# Mainboard.net
KiCad netlist of a schematic drawn in EAGLE
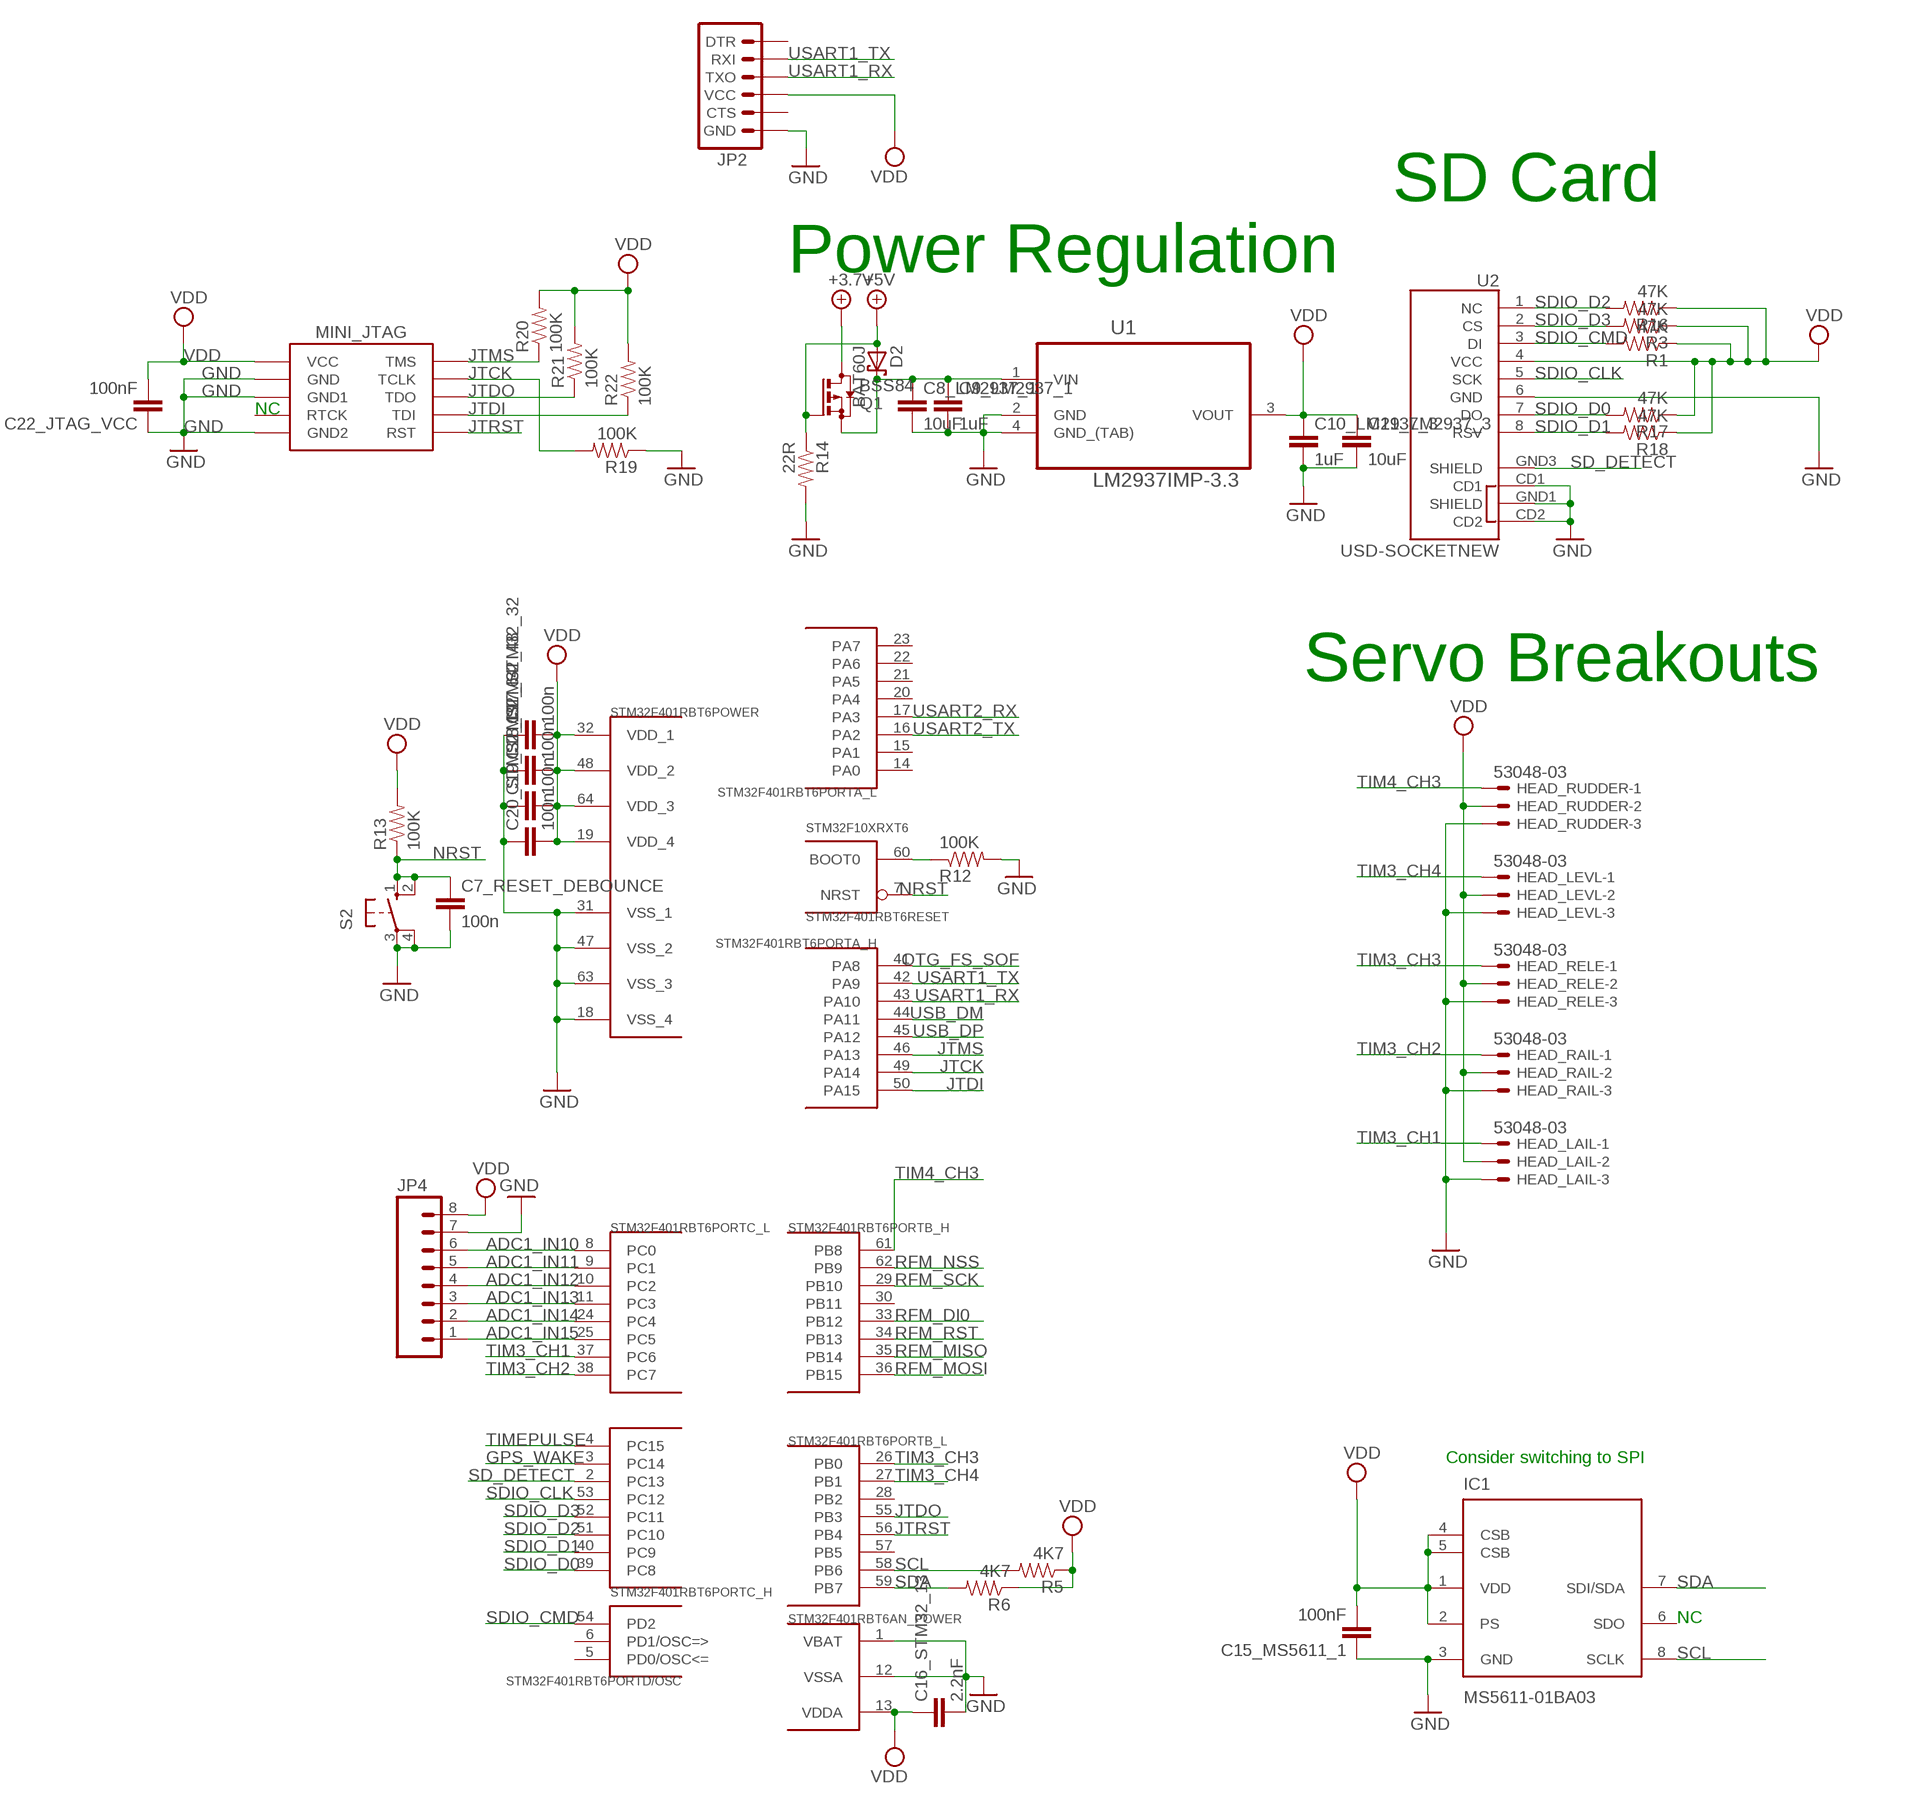
[diagram p0: schematic, sheet 1, part 1 of 2]
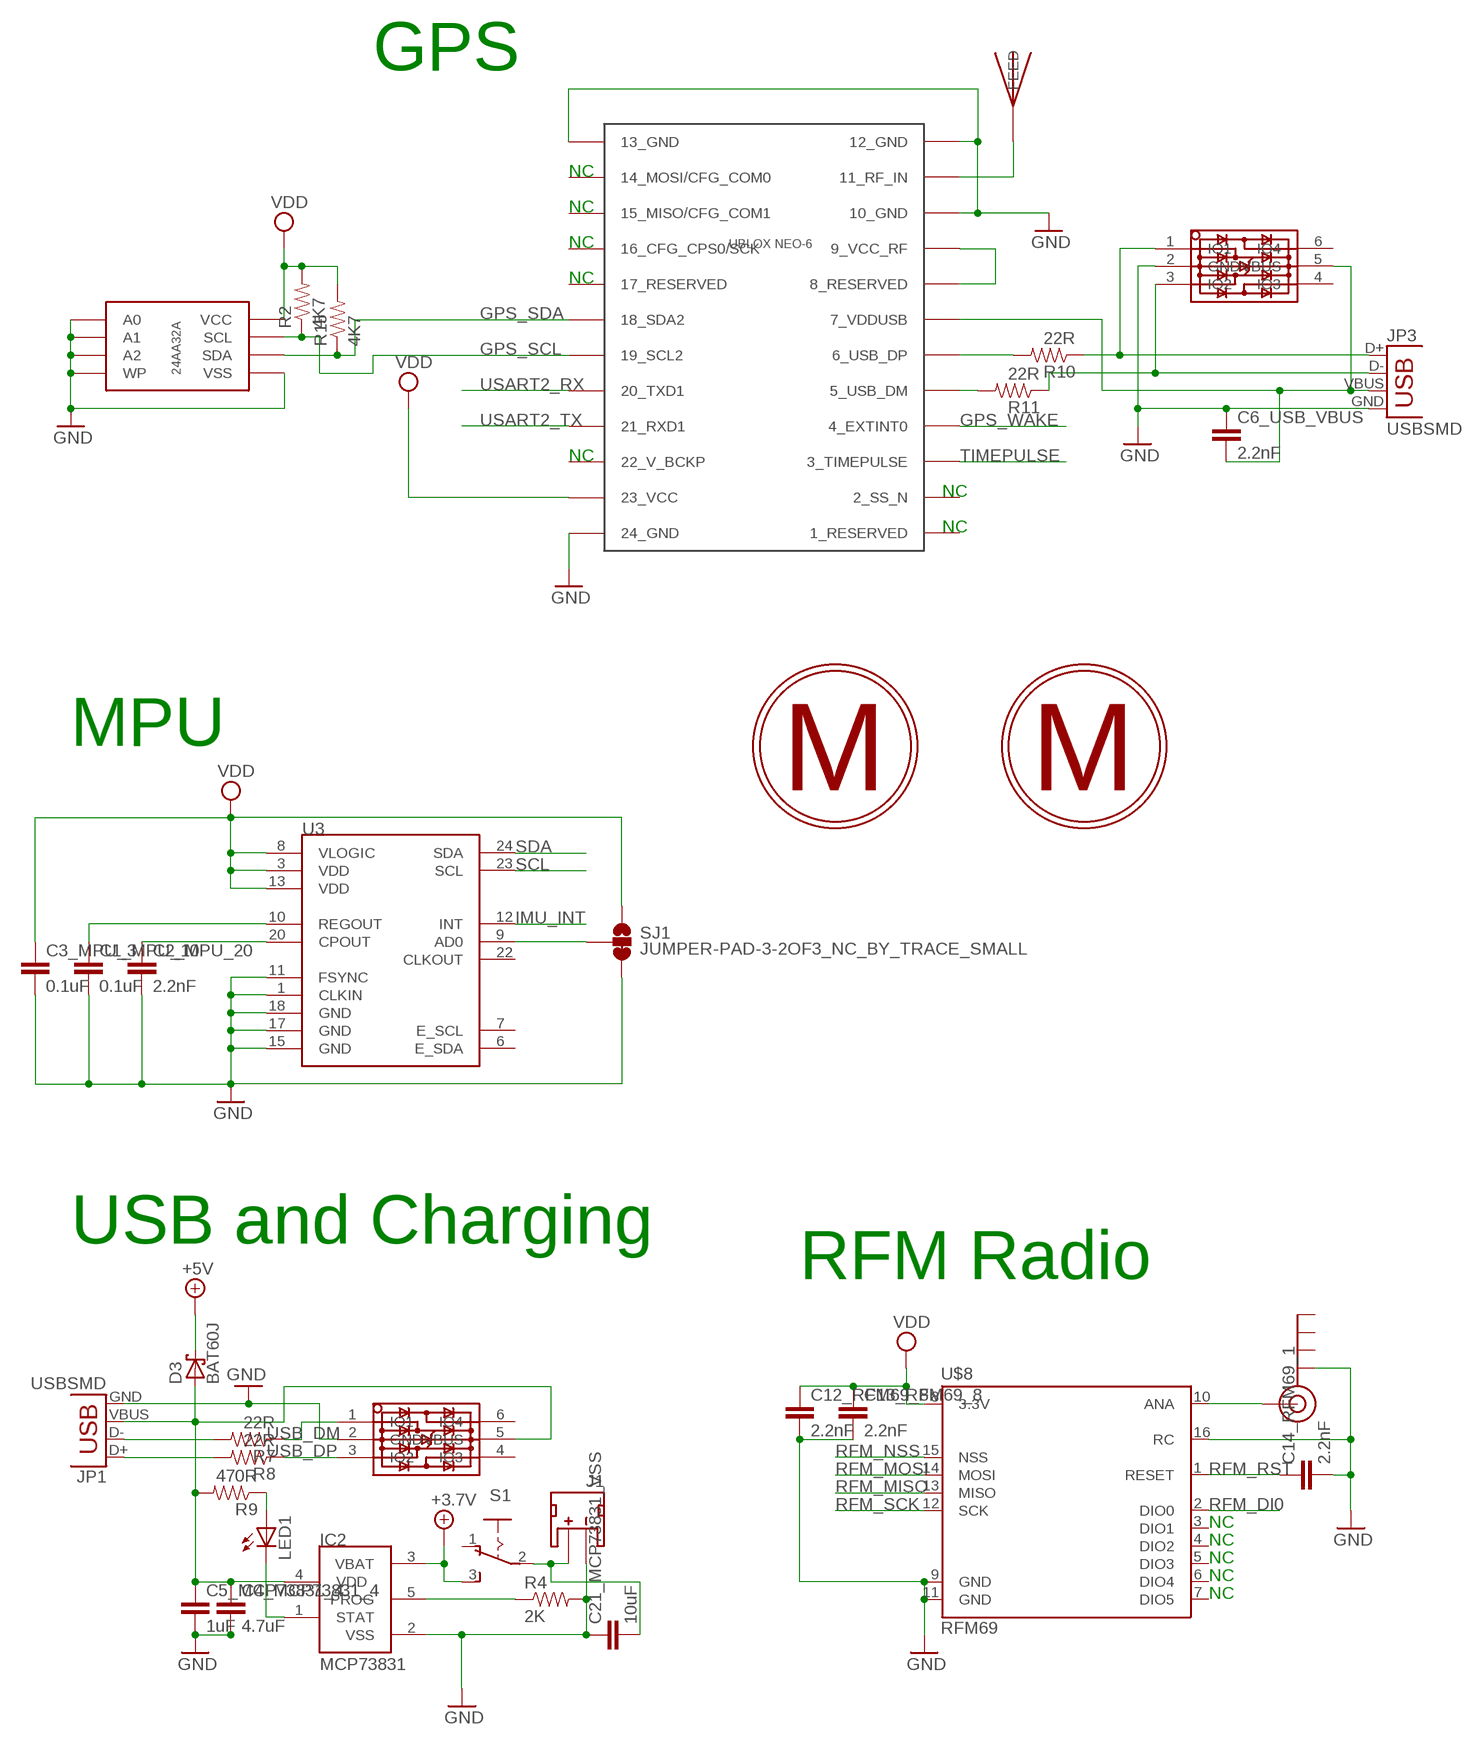
[diagram p1: schematic, sheet 1, part 2 of 2]

(export (version "E")
  (design (tool "Eeschema 10.0.6"))
  (components
    (comp (ref "C1_MPU_10")
      (value "0.1uF")
      (footprint "eagle-import:0805")
      (libsource (lib "eagle-import") (part "CAP0805"))
    )
    (comp (ref "C2_MPU_20")
      (value "2.2nF")
      (footprint "eagle-import:0805")
      (libsource (lib "eagle-import") (part "CAP0805"))
    )
    (comp (ref "C3_MPU_3")
      (value "0.1uF")
      (footprint "eagle-import:0805")
      (libsource (lib "eagle-import") (part "CAP0805"))
    )
    (comp (ref "C4_MCP73831_4")
      (value "4.7uF")
      (footprint "eagle-import:0805")
      (libsource (lib "eagle-import") (part "CAP0805"))
    )
    (comp (ref "C5_MCP73831_4")
      (value "1uF")
      (footprint "eagle-import:0805")
      (libsource (lib "eagle-import") (part "CAP0805"))
    )
    (comp (ref "C6_USB_VBUS")
      (value "2.2nF")
      (footprint "eagle-import:0805")
      (libsource (lib "eagle-import") (part "CAP0805"))
    )
    (comp (ref "C7_RESET_DEBOUNCE")
      (value "100n")
      (footprint "eagle-import:0805")
      (libsource (lib "eagle-import") (part "CAP0805"))
    )
    (comp (ref "C8_LM2937_1")
      (value "10uF")
      (footprint "eagle-import:0805")
      (libsource (lib "eagle-import") (part "CAP0805"))
    )
    (comp (ref "C9_LM2937_1")
      (value "1uF")
      (footprint "eagle-import:0805")
      (libsource (lib "eagle-import") (part "CAP0805"))
    )
    (comp (ref "C10_LM2937_3")
      (value "1uF")
      (footprint "eagle-import:0805")
      (libsource (lib "eagle-import") (part "CAP0805"))
    )
    (comp (ref "C11_LM2937_3")
      (value "10uF")
      (footprint "eagle-import:0805")
      (libsource (lib "eagle-import") (part "CAP0805"))
    )
    (comp (ref "C12_RFM69_8")
      (value "2.2nF")
      (footprint "eagle-import:0805")
      (libsource (lib "eagle-import") (part "CAP0805"))
    )
    (comp (ref "C13_RFM69_8")
      (value "2.2nF")
      (footprint "eagle-import:0805")
      (libsource (lib "eagle-import") (part "CAP0805"))
    )
    (comp (ref "C14_RFM69_1")
      (value "2.2nF")
      (footprint "eagle-import:0805")
      (libsource (lib "eagle-import") (part "CAP0805"))
    )
    (comp (ref "C15_MS5611_1")
      (value "100nF")
      (footprint "eagle-import:0805")
      (libsource (lib "eagle-import") (part "CAP0805"))
    )
    (comp (ref "C16_STM32_13")
      (value "2.2nF")
      (footprint "eagle-import:0805")
      (libsource (lib "eagle-import") (part "CAP0805"))
    )
    (comp (ref "C17_STM32_32")
      (value "100n")
      (footprint "eagle-import:0805")
      (libsource (lib "eagle-import") (part "CAP0805"))
    )
    (comp (ref "C18_STM32_48")
      (value "100n")
      (footprint "eagle-import:0805")
      (libsource (lib "eagle-import") (part "CAP0805"))
    )
    (comp (ref "C19_STM32_64")
      (value "100n")
      (footprint "eagle-import:0805")
      (libsource (lib "eagle-import") (part "CAP0805"))
    )
    (comp (ref "C20_STM32_19")
      (value "100n")
      (footprint "eagle-import:0805")
      (libsource (lib "eagle-import") (part "CAP0805"))
    )
    (comp (ref "C21_MCP73831_VSS")
      (value "10uF")
      (footprint "eagle-import:0805")
      (libsource (lib "eagle-import") (part "CAP0805"))
    )
    (comp (ref "C22_JTAG_VCC")
      (value "100nF")
      (footprint "eagle-import:0805")
      (libsource (lib "eagle-import") (part "CAP0805"))
    )
    (comp (ref "D2")
      (value "BAT60J")
      (footprint "eagle-import:SOD323_ST")
      (libsource (lib "eagle-import") (part "BAT60J"))
    )
    (comp (ref "D3")
      (value "BAT60J")
      (footprint "eagle-import:SOD323_ST")
      (libsource (lib "eagle-import") (part "BAT60J"))
    )
    (comp (ref "HEAD_LAIL")
      (value "53048-03")
      (footprint "eagle-import:53048-03")
      (fields (field (name "MF") "WALDOM/MOLEX") (field (name "MPN") "53048-0310"))
      (libsource (lib "eagle-import") (part "53?-03048"))
    )
    (comp (ref "HEAD_LEVL")
      (value "53048-03")
      (footprint "eagle-import:53048-03")
      (fields (field (name "MF") "WALDOM/MOLEX") (field (name "MPN") "53048-0310"))
      (libsource (lib "eagle-import") (part "53?-03048"))
    )
    (comp (ref "HEAD_RAIL")
      (value "53048-03")
      (footprint "eagle-import:53048-03")
      (fields (field (name "MF") "WALDOM/MOLEX") (field (name "MPN") "53048-0310"))
      (libsource (lib "eagle-import") (part "53?-03048"))
    )
    (comp (ref "HEAD_RELE")
      (value "53048-03")
      (footprint "eagle-import:53048-03")
      (fields (field (name "MF") "WALDOM/MOLEX") (field (name "MPN") "53048-0310"))
      (libsource (lib "eagle-import") (part "53?-03048"))
    )
    (comp (ref "HEAD_RUDDER")
      (value "53048-03")
      (footprint "eagle-import:53048-03")
      (fields (field (name "MF") "WALDOM/MOLEX") (field (name "MPN") "53048-0310"))
      (libsource (lib "eagle-import") (part "53?-03048"))
    )
    (comp (ref "IC1")
      (value "MS5611-01BA03")
      (footprint "eagle-import:SON125P300X500X100-8N")
      (libsource (lib "eagle-import") (part "MS5611-01BA03"))
    )
    (comp (ref "IC2")
      (value "MCP73831")
      (footprint "eagle-import:SOT23-5L")
      (libsource (lib "eagle-import") (part "MCP73831"))
    )
    (comp (ref "J$1")
      (value "SMA_EDGE")
      (footprint "eagle-import:SMA-EDGE")
      (libsource (lib "eagle-import") (part "SMA_EDGE"))
    )
    (comp (ref "J1")
      (value "JST_2MM_MALE")
      (footprint "eagle-import:JST-2-SMD")
      (libsource (lib "eagle-import") (part "JST_2MM_MALE"))
    )
    (comp (ref "JP1")
      (value "USBSMD")
      (footprint "eagle-import:USB-MINIB")
      (libsource (lib "eagle-import") (part "USBSMD"))
    )
    (comp (ref "JP2")
      (value "ARDUINO_SERIAL_PROGRAMSMD")
      (footprint "eagle-import:1X06-SMD")
      (libsource (lib "eagle-import") (part "ARDUINO_SERIAL_PROGRAMSMD"))
    )
    (comp (ref "JP3")
      (value "USBSMD")
      (footprint "eagle-import:USB-MINIB")
      (libsource (lib "eagle-import") (part "USBSMD"))
    )
    (comp (ref "JP4")
      (value "M08BM08B-SRSS-TB")
      (footprint "eagle-import:BM08B-SRSS-TB")
      (libsource (lib "eagle-import") (part "M08BM08B-SRSS-TB"))
    )
    (comp (ref "LED1")
      (value "LEDCHIP-LED0805")
      (footprint "eagle-import:CHIP-LED0805")
      (libsource (lib "eagle-import") (part "LEDCHIP-LED0805"))
    )
    (comp (ref "Q1")
      (value "BSS84")
      (footprint "eagle-import:SOT23")
      (libsource (lib "eagle-import") (part "BSS84"))
    )
    (comp (ref "R1")
      (value "47K")
      (footprint "eagle-import:0805")
      (libsource (lib "eagle-import") (part "RESISTOR0805-RES"))
    )
    (comp (ref "R2")
      (value "4K7")
      (footprint "eagle-import:0805")
      (libsource (lib "eagle-import") (part "RESISTOR0805-RES"))
    )
    (comp (ref "R3")
      (value "47K")
      (footprint "eagle-import:0805")
      (libsource (lib "eagle-import") (part "RESISTOR0805-RES"))
    )
    (comp (ref "R4")
      (value "2K")
      (footprint "eagle-import:0805")
      (libsource (lib "eagle-import") (part "RESISTOR0805-RES"))
    )
    (comp (ref "R5")
      (value "4K7")
      (footprint "eagle-import:0805")
      (libsource (lib "eagle-import") (part "RESISTOR0805-RES"))
    )
    (comp (ref "R6")
      (value "4K7")
      (footprint "eagle-import:0805")
      (libsource (lib "eagle-import") (part "RESISTOR0805-RES"))
    )
    (comp (ref "R7")
      (value "22R")
      (footprint "eagle-import:0805")
      (libsource (lib "eagle-import") (part "RESISTOR0805-RES"))
    )
    (comp (ref "R8")
      (value "22R")
      (footprint "eagle-import:0805")
      (libsource (lib "eagle-import") (part "RESISTOR0805-RES"))
    )
    (comp (ref "R9")
      (value "470R")
      (footprint "eagle-import:0805")
      (libsource (lib "eagle-import") (part "RESISTOR0805-RES"))
    )
    (comp (ref "R10")
      (value "22R")
      (footprint "eagle-import:0805")
      (libsource (lib "eagle-import") (part "RESISTOR0805-RES"))
    )
    (comp (ref "R11")
      (value "22R")
      (footprint "eagle-import:0805")
      (libsource (lib "eagle-import") (part "RESISTOR0805-RES"))
    )
    (comp (ref "R12")
      (value "100K")
      (footprint "eagle-import:0805")
      (libsource (lib "eagle-import") (part "RESISTOR0805-RES"))
    )
    (comp (ref "R13")
      (value "100K")
      (footprint "eagle-import:0805")
      (libsource (lib "eagle-import") (part "RESISTOR0805-RES"))
    )
    (comp (ref "R14")
      (value "22R")
      (footprint "eagle-import:0805")
      (libsource (lib "eagle-import") (part "RESISTOR0805-RES"))
    )
    (comp (ref "R15")
      (value "4K7")
      (footprint "eagle-import:0805")
      (libsource (lib "eagle-import") (part "RESISTOR0805-RES"))
    )
    (comp (ref "R16")
      (value "47K")
      (footprint "eagle-import:0805")
      (libsource (lib "eagle-import") (part "RESISTOR0805-RES"))
    )
    (comp (ref "R17")
      (value "47K")
      (footprint "eagle-import:0805")
      (libsource (lib "eagle-import") (part "RESISTOR0805-RES"))
    )
    (comp (ref "R18")
      (value "47K")
      (footprint "eagle-import:0805")
      (libsource (lib "eagle-import") (part "RESISTOR0805-RES"))
    )
    (comp (ref "R19")
      (value "100K")
      (footprint "eagle-import:0805")
      (libsource (lib "eagle-import") (part "RESISTOR0805-RES"))
    )
    (comp (ref "R20")
      (value "100K")
      (footprint "eagle-import:0805")
      (libsource (lib "eagle-import") (part "RESISTOR0805-RES"))
    )
    (comp (ref "R21")
      (value "100K")
      (footprint "eagle-import:0805")
      (libsource (lib "eagle-import") (part "RESISTOR0805-RES"))
    )
    (comp (ref "R22")
      (value "100K")
      (footprint "eagle-import:0805")
      (libsource (lib "eagle-import") (part "RESISTOR0805-RES"))
    )
    (comp (ref "S1")
      (value "255SB")
      (footprint "eagle-import:255SB")
      (libsource (lib "eagle-import") (part "255SB"))
    )
    (comp (ref "S2")
      (value "10-XX")
      (footprint "eagle-import:B3F-10XX")
      (fields (field (name "MPN") "B3F-1000"))
      (libsource (lib "eagle-import") (part "10-XX"))
    )
    (comp (ref "SJ1")
      (value "JUMPER-PAD-3-2OF3_NC_BY_TRACE_SMALL")
      (footprint "eagle-import:PAD-JUMPER-3-2OF3_NC_BY_TRACE_YES_SILK_FULL_BOX")
      (libsource (lib "eagle-import") (part "JUMPER-PAD-3-2OF3_NC_BY_TRACE_SMALL"))
    )
    (comp (ref "STM32F401RBT6")
      (value "STM32F10XRXT6")
      (footprint "eagle-import:TQFP64")
      (libsource (lib "eagle-import") (part "STM32F10XRXT6"))
    )
    (comp (ref "U$1")
      (value "USBLC6-4")
      (footprint "eagle-import:SOT23-6")
      (libsource (lib "eagle-import") (part "USBLC6-4"))
    )
    (comp (ref "U$2")
      (value "JTAG_MINI")
      (footprint "eagle-import:JTAG_MINI")
      (libsource (lib "eagle-import") (part "JTAG_MINI"))
    )
    (comp (ref "U$3")
      (value "I2C_EEPROM_24AA32A")
      (footprint "eagle-import:MSOP8")
      (libsource (lib "eagle-import") (part "I2C_EEPROM_24AA32A"))
    )
    (comp (ref "U$4")
      (value "JTI_ANTENNA-1575AT43A40")
      (footprint "eagle-import:JTI_ANTENNA-1575AT43A40")
      (libsource (lib "eagle-import") (part "JTI_ANTENNA-1575AT43A40"))
    )
    (comp (ref "U$5")
      (value "UBLOX_NEO-6")
      (footprint "eagle-import:UBLOX_NEO-6P")
      (libsource (lib "eagle-import") (part "UBLOX_NEO-6"))
    )
    (comp (ref "U$6")
      (value "USBLC6-4")
      (footprint "eagle-import:SOT23-6")
      (libsource (lib "eagle-import") (part "USBLC6-4"))
    )
    (comp (ref "U$7")
      (value "SERVO")
      (footprint "eagle-import:HK3D-1.7L")
      (libsource (lib "eagle-import") (part "SERVO"))
    )
    (comp (ref "U$8")
      (value "RFM69")
      (footprint "eagle-import:RFM69SMD")
      (libsource (lib "eagle-import") (part "RFM69"))
    )
    (comp (ref "U$9")
      (value "SERVO")
      (footprint "eagle-import:HK3D-1.7L")
      (libsource (lib "eagle-import") (part "SERVO"))
    )
    (comp (ref "U1")
      (value "LM2937IMP-3.3")
      (footprint "eagle-import:SOT230P700X180-4N")
      (fields (field (name "MPN") "LM2937IMP-5.0"))
      (libsource (lib "eagle-import") (part "LM2937IMP-5.0"))
    )
    (comp (ref "U2")
      (value "USD-SOCKETNEW")
      (footprint "eagle-import:MICRO-SD-SOCKET-PP")
      (libsource (lib "eagle-import") (part "USD-SOCKETNEW"))
    )
    (comp (ref "U3")
      (value "MPU-9150QFN-24-NP")
      (footprint "eagle-import:QFN-24-NP")
      (libsource (lib "eagle-import") (part "MPU-9150QFN-24-NP"))
    )
  )
  (nets
    (net (code "1") (name "+3.7V") (class "Default")
      (node (ref "IC2") (pin "3") (pinfunction "VBAT_3") (pintype "bidirectional"))
      (node (ref "Q1") (pin "3") (pinfunction "D_3") (pintype "passive"))
      (node (ref "S1") (pin "3") (pinfunction "S_3") (pintype "passive"))
    )
    (net (code "2") (name "+5V") (class "Default")
      (node (ref "D2") (pin "A") (pinfunction "A_A") (pintype "passive"))
      (node (ref "D3") (pin "C") (pinfunction "C_C") (pintype "passive"))
      (node (ref "Q1") (pin "1") (pinfunction "G_1") (pintype "passive"))
      (node (ref "R14") (pin "1") (pinfunction "1_1") (pintype "passive"))
    )
    (net (code "3") (name "/ADC1_IN10") (class "Default")
      (node (ref "JP4") (pin "6") (pinfunction "6_6") (pintype "passive"))
      (node (ref "STM32F401RBT6") (pin "8") (pinfunction "PC0_8") (pintype "bidirectional"))
    )
    (net (code "4") (name "/ADC1_IN11") (class "Default")
      (node (ref "JP4") (pin "5") (pinfunction "5_5") (pintype "passive"))
      (node (ref "STM32F401RBT6") (pin "9") (pinfunction "PC1_9") (pintype "bidirectional"))
    )
    (net (code "5") (name "/ADC1_IN12") (class "Default")
      (node (ref "JP4") (pin "4") (pinfunction "4_4") (pintype "passive"))
      (node (ref "STM32F401RBT6") (pin "10") (pinfunction "PC2_10") (pintype "bidirectional"))
    )
    (net (code "6") (name "/ADC1_IN13") (class "Default")
      (node (ref "JP4") (pin "3") (pinfunction "3_3") (pintype "passive"))
      (node (ref "STM32F401RBT6") (pin "11") (pinfunction "PC3_11") (pintype "bidirectional"))
    )
    (net (code "7") (name "/ADC1_IN14") (class "Default")
      (node (ref "JP4") (pin "2") (pinfunction "2_2") (pintype "passive"))
      (node (ref "STM32F401RBT6") (pin "24") (pinfunction "PC4_24") (pintype "bidirectional"))
    )
    (net (code "8") (name "/ADC1_IN15") (class "Default")
      (node (ref "JP4") (pin "1") (pinfunction "1_1") (pintype "passive"))
      (node (ref "STM32F401RBT6") (pin "25") (pinfunction "PC5_25") (pintype "bidirectional"))
    )
    (net (code "9") (name "/GPS_SCL") (class "Default")
      (node (ref "R2") (pin "1") (pinfunction "1_1") (pintype "passive"))
      (node (ref "U$3") (pin "6") (pinfunction "SCL_6") (pintype "bidirectional"))
      (node (ref "U$5") (pin "19_SCL2") (pinfunction "19_SCL2_19_SCL2") (pintype "bidirectional"))
    )
    (net (code "10") (name "/GPS_SDA") (class "Default")
      (node (ref "R15") (pin "1") (pinfunction "1_1") (pintype "passive"))
      (node (ref "U$3") (pin "5") (pinfunction "SDA_5") (pintype "bidirectional"))
      (node (ref "U$5") (pin "18_SDA2") (pinfunction "18_SDA2_18_SDA2") (pintype "bidirectional"))
    )
    (net (code "11") (name "/GPS_WAKE") (class "Default")
      (node (ref "STM32F401RBT6") (pin "3") (pinfunction "PC14_3") (pintype "bidirectional"))
      (node (ref "U$5") (pin "4_EXTINT0") (pinfunction "4_EXTINT0_4_EXTINT0") (pintype "bidirectional"))
    )
    (net (code "12") (name "/IMU_INT") (class "Default")
      (node (ref "U3") (pin "12") (pinfunction "INT_12") (pintype "bidirectional"))
    )
    (net (code "13") (name "/JTCK") (class "Default")
      (node (ref "R19") (pin "2") (pinfunction "2_2") (pintype "passive"))
      (node (ref "STM32F401RBT6") (pin "49") (pinfunction "PA14_49") (pintype "bidirectional"))
      (node (ref "U$2") (pin "4") (pinfunction "TCLK_4") (pintype "bidirectional"))
    )
    (net (code "14") (name "/JTDI") (class "Default")
      (node (ref "R22") (pin "1") (pinfunction "1_1") (pintype "passive"))
      (node (ref "STM32F401RBT6") (pin "50") (pinfunction "PA15_50") (pintype "bidirectional"))
      (node (ref "U$2") (pin "8") (pinfunction "TDI_8") (pintype "bidirectional"))
    )
    (net (code "15") (name "/JTDO") (class "Default")
      (node (ref "R21") (pin "1") (pinfunction "1_1") (pintype "passive"))
      (node (ref "STM32F401RBT6") (pin "55") (pinfunction "PB3_55") (pintype "bidirectional"))
      (node (ref "U$2") (pin "6") (pinfunction "TDO_6") (pintype "bidirectional"))
    )
    (net (code "16") (name "/JTMS") (class "Default")
      (node (ref "R20") (pin "1") (pinfunction "1_1") (pintype "passive"))
      (node (ref "STM32F401RBT6") (pin "46") (pinfunction "PA13_46") (pintype "bidirectional"))
      (node (ref "U$2") (pin "2") (pinfunction "TMS_2") (pintype "bidirectional"))
    )
    (net (code "17") (name "/JTRST") (class "Default")
      (node (ref "STM32F401RBT6") (pin "56") (pinfunction "PB4_56") (pintype "bidirectional"))
      (node (ref "U$2") (pin "10") (pinfunction "RST_10") (pintype "bidirectional"))
    )
    (net (code "18") (name "/NRST") (class "Default")
      (node (ref "C7_RESET_DEBOUNCE") (pin "1") (pinfunction "1_1") (pintype "passive"))
      (node (ref "R13") (pin "1") (pinfunction "1_1") (pintype "passive"))
      (node (ref "S2") (pin "1") (pinfunction "S_1") (pintype "passive"))
      (node (ref "S2") (pin "2") (pinfunction "S1_2") (pintype "passive"))
      (node (ref "STM32F401RBT6") (pin "7") (pinfunction "NRST_7") (pintype "input"))
    )
    (net (code "19") (name "/OTG_FS_SOF") (class "Default")
      (node (ref "STM32F401RBT6") (pin "41") (pinfunction "PA8_41") (pintype "bidirectional"))
    )
    (net (code "20") (name "/RFM_DI0") (class "Default")
      (node (ref "STM32F401RBT6") (pin "33") (pinfunction "PB12_33") (pintype "bidirectional"))
      (node (ref "U$8") (pin "2") (pinfunction "DIO0_2") (pintype "bidirectional"))
    )
    (net (code "21") (name "/RFM_MISO") (class "Default")
      (node (ref "STM32F401RBT6") (pin "35") (pinfunction "PB14_35") (pintype "bidirectional"))
      (node (ref "U$8") (pin "13") (pinfunction "MISO_13") (pintype "output"))
    )
    (net (code "22") (name "/RFM_MOSI") (class "Default")
      (node (ref "STM32F401RBT6") (pin "36") (pinfunction "PB15_36") (pintype "bidirectional"))
      (node (ref "U$8") (pin "14") (pinfunction "MOSI_14") (pintype "input"))
    )
    (net (code "23") (name "/RFM_NSS") (class "Default")
      (node (ref "STM32F401RBT6") (pin "62") (pinfunction "PB9_62") (pintype "bidirectional"))
      (node (ref "U$8") (pin "15") (pinfunction "NSS_15") (pintype "input"))
    )
    (net (code "24") (name "/RFM_RST") (class "Default")
      (node (ref "C14_RFM69_1") (pin "1") (pinfunction "1_1") (pintype "passive"))
      (node (ref "STM32F401RBT6") (pin "34") (pinfunction "PB13_34") (pintype "bidirectional"))
      (node (ref "U$8") (pin "1") (pinfunction "RESET_1") (pintype "input"))
    )
    (net (code "25") (name "/RFM_SCK") (class "Default")
      (node (ref "STM32F401RBT6") (pin "29") (pinfunction "PB10_29") (pintype "bidirectional"))
      (node (ref "U$8") (pin "12") (pinfunction "SCK_12") (pintype "input"))
    )
    (net (code "26") (name "/SCL") (class "Default")
      (node (ref "IC1") (pin "8") (pinfunction "SCLK_8") (pintype "input"))
      (node (ref "R5") (pin "2") (pinfunction "2_2") (pintype "passive"))
      (node (ref "STM32F401RBT6") (pin "58") (pinfunction "PB6_58") (pintype "bidirectional"))
      (node (ref "U3") (pin "23") (pinfunction "SCL_23") (pintype "bidirectional"))
    )
    (net (code "27") (name "/SDA") (class "Default")
      (node (ref "IC1") (pin "7") (pinfunction "SDI/SDA_7") (pintype "bidirectional"))
      (node (ref "R6") (pin "2") (pinfunction "2_2") (pintype "passive"))
      (node (ref "STM32F401RBT6") (pin "59") (pinfunction "PB7_59") (pintype "bidirectional"))
      (node (ref "U3") (pin "24") (pinfunction "SDA_24") (pintype "bidirectional"))
    )
    (net (code "28") (name "/SDIO_CLK") (class "Default")
      (node (ref "STM32F401RBT6") (pin "53") (pinfunction "PC12_53") (pintype "bidirectional"))
      (node (ref "U2") (pin "5") (pinfunction "SCK_5") (pintype "bidirectional"))
    )
    (net (code "29") (name "/SDIO_CMD") (class "Default")
      (node (ref "R1") (pin "2") (pinfunction "2_2") (pintype "passive"))
      (node (ref "STM32F401RBT6") (pin "54") (pinfunction "PD2_54") (pintype "bidirectional"))
      (node (ref "U2") (pin "3") (pinfunction "DI_3") (pintype "bidirectional"))
    )
    (net (code "30") (name "/SDIO_D0") (class "Default")
      (node (ref "R17") (pin "2") (pinfunction "2_2") (pintype "passive"))
      (node (ref "STM32F401RBT6") (pin "39") (pinfunction "PC8_39") (pintype "bidirectional"))
      (node (ref "U2") (pin "7") (pinfunction "DO_7") (pintype "bidirectional"))
    )
    (net (code "31") (name "/SDIO_D1") (class "Default")
      (node (ref "R18") (pin "2") (pinfunction "2_2") (pintype "passive"))
      (node (ref "STM32F401RBT6") (pin "40") (pinfunction "PC9_40") (pintype "bidirectional"))
      (node (ref "U2") (pin "8") (pinfunction "RSV_8") (pintype "bidirectional"))
    )
    (net (code "32") (name "/SDIO_D2") (class "Default")
      (node (ref "R16") (pin "2") (pinfunction "2_2") (pintype "passive"))
      (node (ref "STM32F401RBT6") (pin "51") (pinfunction "PC10_51") (pintype "bidirectional"))
      (node (ref "U2") (pin "1") (pinfunction "NC_1") (pintype "bidirectional"))
    )
    (net (code "33") (name "/SDIO_D3") (class "Default")
      (node (ref "R3") (pin "2") (pinfunction "2_2") (pintype "passive"))
      (node (ref "STM32F401RBT6") (pin "52") (pinfunction "PC11_52") (pintype "bidirectional"))
      (node (ref "U2") (pin "2") (pinfunction "CS_2") (pintype "bidirectional"))
    )
    (net (code "34") (name "/SD_DETECT") (class "Default")
      (node (ref "STM32F401RBT6") (pin "2") (pinfunction "PC13_2") (pintype "bidirectional"))
      (node (ref "U2") (pin "GND3") (pinfunction "SHIELD_GND3") (pintype "bidirectional"))
    )
    (net (code "35") (name "/TIM3_CH1") (class "Default")
      (node (ref "HEAD_LAIL") (pin "1") (pinfunction "S_1") (pintype "passive"))
      (node (ref "STM32F401RBT6") (pin "37") (pinfunction "PC6_37") (pintype "bidirectional"))
    )
    (net (code "36") (name "/TIM3_CH2") (class "Default")
      (node (ref "HEAD_RAIL") (pin "1") (pinfunction "S_1") (pintype "passive"))
      (node (ref "STM32F401RBT6") (pin "38") (pinfunction "PC7_38") (pintype "bidirectional"))
    )
    (net (code "37") (name "/TIM3_CH3") (class "Default")
      (node (ref "HEAD_RELE") (pin "1") (pinfunction "S_1") (pintype "passive"))
      (node (ref "STM32F401RBT6") (pin "26") (pinfunction "PB0_26") (pintype "bidirectional"))
    )
    (net (code "38") (name "/TIM3_CH4") (class "Default")
      (node (ref "HEAD_LEVL") (pin "1") (pinfunction "S_1") (pintype "passive"))
      (node (ref "STM32F401RBT6") (pin "27") (pinfunction "PB1_27") (pintype "bidirectional"))
    )
    (net (code "39") (name "/TIM4_CH3") (class "Default")
      (node (ref "HEAD_RUDDER") (pin "1") (pinfunction "S_1") (pintype "passive"))
      (node (ref "STM32F401RBT6") (pin "61") (pinfunction "PB8_61") (pintype "bidirectional"))
    )
    (net (code "40") (name "/TIMEPULSE") (class "Default")
      (node (ref "STM32F401RBT6") (pin "4") (pinfunction "PC15_4") (pintype "bidirectional"))
      (node (ref "U$5") (pin "3_TIMEPULSE") (pinfunction "3_TIMEPULSE_3_TIMEPULSE") (pintype "bidirectional"))
    )
    (net (code "41") (name "/USART1_RX") (class "Default")
      (node (ref "JP2") (pin "3") (pinfunction "TXO_3") (pintype "passive"))
      (node (ref "STM32F401RBT6") (pin "43") (pinfunction "PA10_43") (pintype "bidirectional"))
    )
    (net (code "42") (name "/USART1_TX") (class "Default")
      (node (ref "JP2") (pin "2") (pinfunction "RXI_2") (pintype "passive"))
      (node (ref "STM32F401RBT6") (pin "42") (pinfunction "PA9_42") (pintype "bidirectional"))
    )
    (net (code "43") (name "/USART2_RX") (class "Default")
      (node (ref "STM32F401RBT6") (pin "17") (pinfunction "PA3_17") (pintype "bidirectional"))
      (node (ref "U$5") (pin "20_TXD1") (pinfunction "20_TXD1_20_TXD1") (pintype "bidirectional"))
    )
    (net (code "44") (name "/USART2_TX") (class "Default")
      (node (ref "STM32F401RBT6") (pin "16") (pinfunction "PA2_16") (pintype "bidirectional"))
      (node (ref "U$5") (pin "21_RXD1") (pinfunction "21_RXD1_21_RXD1") (pintype "bidirectional"))
    )
    (net (code "45") (name "/USB_DM") (class "Default")
      (node (ref "R7") (pin "1") (pinfunction "1_1") (pintype "passive"))
      (node (ref "STM32F401RBT6") (pin "44") (pinfunction "PA11_44") (pintype "bidirectional"))
      (node (ref "U$6") (pin "1") (pinfunction "IO1_1") (pintype "bidirectional"))
    )
    (net (code "46") (name "/USB_DP") (class "Default")
      (node (ref "R8") (pin "1") (pinfunction "1_1") (pintype "passive"))
      (node (ref "STM32F401RBT6") (pin "45") (pinfunction "PA12_45") (pintype "bidirectional"))
      (node (ref "U$6") (pin "3") (pinfunction "IO2_3") (pintype "bidirectional"))
    )
    (net (code "47") (name "GND") (class "Default")
      (node (ref "C10_LM2937_3") (pin "2") (pinfunction "2_2") (pintype "passive"))
      (node (ref "C11_LM2937_3") (pin "2") (pinfunction "2_2") (pintype "passive"))
      (node (ref "C12_RFM69_8") (pin "2") (pinfunction "2_2") (pintype "passive"))
      (node (ref "C13_RFM69_8") (pin "2") (pinfunction "2_2") (pintype "passive"))
      (node (ref "C14_RFM69_1") (pin "2") (pinfunction "2_2") (pintype "passive"))
      (node (ref "C15_MS5611_1") (pin "1") (pinfunction "1_1") (pintype "passive"))
      (node (ref "C16_STM32_13") (pin "2") (pinfunction "2_2") (pintype "passive"))
      (node (ref "C17_STM32_32") (pin "1") (pinfunction "1_1") (pintype "passive"))
      (node (ref "C18_STM32_48") (pin "1") (pinfunction "1_1") (pintype "passive"))
      (node (ref "C19_STM32_64") (pin "1") (pinfunction "1_1") (pintype "passive"))
      (node (ref "C1_MPU_10") (pin "2") (pinfunction "2_2") (pintype "passive"))
      (node (ref "C20_STM32_19") (pin "1") (pinfunction "1_1") (pintype "passive"))
      (node (ref "C21_MCP73831_VSS") (pin "1") (pinfunction "1_1") (pintype "passive"))
      (node (ref "C22_JTAG_VCC") (pin "1") (pinfunction "1_1") (pintype "passive"))
      (node (ref "C2_MPU_20") (pin "2") (pinfunction "2_2") (pintype "passive"))
      (node (ref "C3_MPU_3") (pin "2") (pinfunction "2_2") (pintype "passive"))
      (node (ref "C4_MCP73831_4") (pin "2") (pinfunction "2_2") (pintype "passive"))
      (node (ref "C5_MCP73831_4") (pin "2") (pinfunction "2_2") (pintype "passive"))
      (node (ref "C6_USB_VBUS") (pin "1") (pinfunction "1_1") (pintype "passive"))
      (node (ref "C7_RESET_DEBOUNCE") (pin "2") (pinfunction "2_2") (pintype "passive"))
      (node (ref "C8_LM2937_1") (pin "2") (pinfunction "2_2") (pintype "passive"))
      (node (ref "C9_LM2937_1") (pin "2") (pinfunction "2_2") (pintype "passive"))
      (node (ref "HEAD_LAIL") (pin "3") (pinfunction "S_3") (pintype "passive"))
      (node (ref "HEAD_LEVL") (pin "3") (pinfunction "S_3") (pintype "passive"))
      (node (ref "HEAD_RAIL") (pin "3") (pinfunction "S_3") (pintype "passive"))
      (node (ref "HEAD_RELE") (pin "3") (pinfunction "S_3") (pintype "passive"))
      (node (ref "HEAD_RUDDER") (pin "3") (pinfunction "S_3") (pintype "passive"))
      (node (ref "IC1") (pin "3") (pinfunction "GND_3") (pintype "power_in"))
      (node (ref "IC2") (pin "2") (pinfunction "VSS_2") (pintype "bidirectional"))
      (node (ref "J$1") (pin "GND@0") (pinfunction "GND_GND@0") (pintype "bidirectional"))
      (node (ref "J1") (pin "1") (pinfunction "-_1") (pintype "bidirectional"))
      (node (ref "JP1") (pin "GND") (pinfunction "GND_GND") (pintype "bidirectional"))
      (node (ref "JP2") (pin "6") (pinfunction "GND_6") (pintype "passive"))
      (node (ref "JP3") (pin "GND") (pinfunction "GND_GND") (pintype "bidirectional"))
      (node (ref "JP4") (pin "7") (pinfunction "7_7") (pintype "passive"))
      (node (ref "R12") (pin "2") (pinfunction "2_2") (pintype "passive"))
      (node (ref "R14") (pin "2") (pinfunction "2_2") (pintype "passive"))
      (node (ref "R19") (pin "1") (pinfunction "1_1") (pintype "passive"))
      (node (ref "R4") (pin "2") (pinfunction "2_2") (pintype "passive"))
      (node (ref "S2") (pin "3") (pinfunction "P_3") (pintype "passive"))
      (node (ref "S2") (pin "4") (pinfunction "P1_4") (pintype "passive"))
      (node (ref "SJ1") (pin "3") (pinfunction "3_3") (pintype "passive"))
      (node (ref "STM32F401RBT6") (pin "1") (pinfunction "VBAT_1") (pintype "power_in"))
      (node (ref "STM32F401RBT6") (pin "12") (pinfunction "VSSA_12") (pintype "power_in"))
      (node (ref "STM32F401RBT6") (pin "18") (pinfunction "VSS_4_18") (pintype "power_in"))
      (node (ref "STM32F401RBT6") (pin "31") (pinfunction "VSS_1_31") (pintype "power_in"))
      (node (ref "STM32F401RBT6") (pin "47") (pinfunction "VSS_2_47") (pintype "power_in"))
      (node (ref "STM32F401RBT6") (pin "63") (pinfunction "VSS_3_63") (pintype "power_in"))
      (node (ref "U$1") (pin "2") (pinfunction "GND_2") (pintype "power_in"))
      (node (ref "U$2") (pin "3") (pinfunction "GND_3") (pintype "bidirectional"))
      (node (ref "U$2") (pin "5") (pinfunction "GND1_5") (pintype "bidirectional"))
      (node (ref "U$2") (pin "9") (pinfunction "GND2_9") (pintype "bidirectional"))
      (node (ref "U$3") (pin "1") (pinfunction "A0_1") (pintype "bidirectional"))
      (node (ref "U$3") (pin "2") (pinfunction "A1_2") (pintype "bidirectional"))
      (node (ref "U$3") (pin "3") (pinfunction "A2_3") (pintype "bidirectional"))
      (node (ref "U$3") (pin "4") (pinfunction "VSS_4") (pintype "bidirectional"))
      (node (ref "U$3") (pin "7") (pinfunction "WP_7") (pintype "bidirectional"))
      (node (ref "U$5") (pin "10_GND") (pinfunction "10_GND_10_GND") (pintype "bidirectional"))
      (node (ref "U$5") (pin "12_GND") (pinfunction "12_GND_12_GND") (pintype "bidirectional"))
      (node (ref "U$5") (pin "13_GND") (pinfunction "13_GND_13_GND") (pintype "bidirectional"))
      (node (ref "U$5") (pin "24_GND") (pinfunction "24_GND_24_GND") (pintype "bidirectional"))
      (node (ref "U$6") (pin "2") (pinfunction "GND_2") (pintype "power_in"))
      (node (ref "U$8") (pin "11") (pinfunction "GND_11") (pintype "power_in"))
      (node (ref "U$8") (pin "16") (pinfunction "RC_16") (pintype "power_in"))
      (node (ref "U$8") (pin "9") (pinfunction "GND_9") (pintype "power_in"))
      (node (ref "U1") (pin "2") (pinfunction "GND_2") (pintype "passive"))
      (node (ref "U1") (pin "4") (pinfunction "GND_(TAB)_4") (pintype "passive"))
      (node (ref "U2") (pin "6") (pinfunction "GND_6") (pintype "bidirectional"))
      (node (ref "U2") (pin "CD1") (pinfunction "CD1_CD1") (pintype "bidirectional"))
      (node (ref "U2") (pin "CD2") (pinfunction "CD2_CD2") (pintype "bidirectional"))
      (node (ref "U2") (pin "GND1") (pinfunction "SHIELD_GND1") (pintype "bidirectional"))
      (node (ref "U3") (pin "1") (pinfunction "CLKIN_1") (pintype "bidirectional"))
      (node (ref "U3") (pin "11") (pinfunction "FSYNC_11") (pintype "bidirectional"))
      (node (ref "U3") (pin "15") (pinfunction "GND_15") (pintype "bidirectional"))
      (node (ref "U3") (pin "17") (pinfunction "GND_17") (pintype "bidirectional"))
      (node (ref "U3") (pin "18") (pinfunction "GND_18") (pintype "bidirectional"))
    )
    (net (code "48") (name "Net-(IC2-PROG)") (class "Default")
      (node (ref "IC2") (pin "5") (pinfunction "PROG_5") (pintype "bidirectional"))
      (node (ref "R4") (pin "1") (pinfunction "1_1") (pintype "passive"))
    )
    (net (code "49") (name "Net-(IC2-STAT)") (class "Default")
      (node (ref "IC2") (pin "1") (pinfunction "STAT_1") (pintype "bidirectional"))
      (node (ref "LED1") (pin "C") (pinfunction "C_C") (pintype "passive"))
    )
    (net (code "50") (name "Net-(IC2-VDD)") (class "Default")
      (node (ref "C4_MCP73831_4") (pin "1") (pinfunction "1_1") (pintype "passive"))
      (node (ref "C5_MCP73831_4") (pin "1") (pinfunction "1_1") (pintype "passive"))
      (node (ref "D3") (pin "A") (pinfunction "A_A") (pintype "passive"))
      (node (ref "IC2") (pin "4") (pinfunction "VDD_4") (pintype "bidirectional"))
      (node (ref "JP1") (pin "VBUS") (pinfunction "VBUS_VBUS") (pintype "bidirectional"))
      (node (ref "R9") (pin "2") (pinfunction "2_2") (pintype "passive"))
      (node (ref "U$6") (pin "5") (pinfunction "VBUS_5") (pintype "power_in"))
    )
    (net (code "51") (name "Net-(J$1-SIGNAL)") (class "Default")
      (node (ref "J$1") (pin "SIG") (pinfunction "SIGNAL_SIG") (pintype "bidirectional"))
      (node (ref "U$8") (pin "10") (pinfunction "ANA_10") (pintype "bidirectional"))
    )
    (net (code "52") (name "Net-(J1-+)") (class "Default")
      (node (ref "C21_MCP73831_VSS") (pin "2") (pinfunction "2_2") (pintype "passive"))
      (node (ref "J1") (pin "2") (pinfunction "+_2") (pintype "bidirectional"))
      (node (ref "S1") (pin "2") (pinfunction "P_2") (pintype "passive"))
    )
    (net (code "53") (name "Net-(JP1-PadD+)") (class "Default")
      (node (ref "JP1") (pin "D+") (pinfunction "D+_D+") (pintype "bidirectional"))
      (node (ref "R8") (pin "2") (pinfunction "2_2") (pintype "passive"))
    )
    (net (code "54") (name "Net-(JP1-PadD-)") (class "Default")
      (node (ref "JP1") (pin "D-") (pinfunction "D-_D-") (pintype "bidirectional"))
      (node (ref "R7") (pin "2") (pinfunction "2_2") (pintype "passive"))
    )
    (net (code "55") (name "Net-(LED1-PadA)") (class "Default")
      (node (ref "LED1") (pin "A") (pinfunction "A_A") (pintype "passive"))
      (node (ref "R9") (pin "1") (pinfunction "1_1") (pintype "passive"))
    )
    (net (code "56") (name "Net-(Q1-S)") (class "Default")
      (node (ref "C8_LM2937_1") (pin "1") (pinfunction "1_1") (pintype "passive"))
      (node (ref "C9_LM2937_1") (pin "1") (pinfunction "1_1") (pintype "passive"))
      (node (ref "D2") (pin "C") (pinfunction "C_C") (pintype "passive"))
      (node (ref "Q1") (pin "2") (pinfunction "S_2") (pintype "passive"))
      (node (ref "U1") (pin "1") (pinfunction "VIN_1") (pintype "input"))
    )
    (net (code "57") (name "Net-(R10-Pad2)") (class "Default")
      (node (ref "R10") (pin "2") (pinfunction "2_2") (pintype "passive"))
      (node (ref "U$5") (pin "6_USB_DP") (pinfunction "6_USB_DP_6_USB_DP") (pintype "bidirectional"))
    )
    (net (code "58") (name "Net-(R11-Pad2)") (class "Default")
      (node (ref "R11") (pin "2") (pinfunction "2_2") (pintype "passive"))
      (node (ref "U$5") (pin "5_USB_DM") (pinfunction "5_USB_DM_5_USB_DM") (pintype "bidirectional"))
    )
    (net (code "59") (name "Net-(STM32F401RBT6J-BOOT0)") (class "Default")
      (node (ref "R12") (pin "1") (pinfunction "1_1") (pintype "passive"))
      (node (ref "STM32F401RBT6") (pin "60") (pinfunction "BOOT0_60") (pintype "input"))
    )
    (net (code "60") (name "Net-(U$1-IO1)") (class "Default")
      (node (ref "JP3") (pin "D+") (pinfunction "D+_D+") (pintype "bidirectional"))
      (node (ref "R10") (pin "1") (pinfunction "1_1") (pintype "passive"))
      (node (ref "U$1") (pin "1") (pinfunction "IO1_1") (pintype "bidirectional"))
    )
    (net (code "61") (name "Net-(U$1-IO2)") (class "Default")
      (node (ref "JP3") (pin "D-") (pinfunction "D-_D-") (pintype "bidirectional"))
      (node (ref "R11") (pin "1") (pinfunction "1_1") (pintype "passive"))
      (node (ref "U$1") (pin "3") (pinfunction "IO2_3") (pintype "bidirectional"))
    )
    (net (code "62") (name "Net-(U$1-VBUS)") (class "Default")
      (node (ref "C6_USB_VBUS") (pin "2") (pinfunction "2_2") (pintype "passive"))
      (node (ref "JP3") (pin "VBUS") (pinfunction "VBUS_VBUS") (pintype "bidirectional"))
      (node (ref "U$1") (pin "5") (pinfunction "VBUS_5") (pintype "power_in"))
      (node (ref "U$5") (pin "7_VDDUSB") (pinfunction "7_VDDUSB_7_VDDUSB") (pintype "bidirectional"))
    )
    (net (code "63") (name "Net-(U$4-PadFEED)") (class "Default")
      (node (ref "U$4") (pin "FEED") (pinfunction "FEED_FEED") (pintype "bidirectional"))
      (node (ref "U$5") (pin "11_RF_IN") (pinfunction "11_RF_IN_11_RF_IN") (pintype "bidirectional"))
    )
    (net (code "64") (name "Net-(U$5-Pad8_RESERVED)") (class "Default")
      (node (ref "U$5") (pin "8_RESERVED") (pinfunction "8_RESERVED_8_RESERVED") (pintype "bidirectional"))
      (node (ref "U$5") (pin "9_VCC_RF") (pinfunction "9_VCC_RF_9_VCC_RF") (pintype "bidirectional"))
    )
    (net (code "65") (name "Net-(U3-AD0)") (class "Default")
      (node (ref "SJ1") (pin "2") (pinfunction "2_2") (pintype "passive"))
      (node (ref "U3") (pin "9") (pinfunction "AD0_9") (pintype "bidirectional"))
    )
    (net (code "66") (name "Net-(U3-CPOUT)") (class "Default")
      (node (ref "C2_MPU_20") (pin "1") (pinfunction "1_1") (pintype "passive"))
      (node (ref "U3") (pin "20") (pinfunction "CPOUT_20") (pintype "bidirectional"))
    )
    (net (code "67") (name "Net-(U3-REGOUT)") (class "Default")
      (node (ref "C1_MPU_10") (pin "1") (pinfunction "1_1") (pintype "passive"))
      (node (ref "U3") (pin "10") (pinfunction "REGOUT_10") (pintype "bidirectional"))
    )
    (net (code "68") (name "VDD") (class "Default")
      (node (ref "C10_LM2937_3") (pin "1") (pinfunction "1_1") (pintype "passive"))
      (node (ref "C11_LM2937_3") (pin "1") (pinfunction "1_1") (pintype "passive"))
      (node (ref "C12_RFM69_8") (pin "1") (pinfunction "1_1") (pintype "passive"))
      (node (ref "C13_RFM69_8") (pin "1") (pinfunction "1_1") (pintype "passive"))
      (node (ref "C15_MS5611_1") (pin "2") (pinfunction "2_2") (pintype "passive"))
      (node (ref "C16_STM32_13") (pin "1") (pinfunction "1_1") (pintype "passive"))
      (node (ref "C17_STM32_32") (pin "2") (pinfunction "2_2") (pintype "passive"))
      (node (ref "C18_STM32_48") (pin "2") (pinfunction "2_2") (pintype "passive"))
      (node (ref "C19_STM32_64") (pin "2") (pinfunction "2_2") (pintype "passive"))
      (node (ref "C20_STM32_19") (pin "2") (pinfunction "2_2") (pintype "passive"))
      (node (ref "C22_JTAG_VCC") (pin "2") (pinfunction "2_2") (pintype "passive"))
      (node (ref "C3_MPU_3") (pin "1") (pinfunction "1_1") (pintype "passive"))
      (node (ref "HEAD_LAIL") (pin "2") (pinfunction "S_2") (pintype "passive"))
      (node (ref "HEAD_LEVL") (pin "2") (pinfunction "S_2") (pintype "passive"))
      (node (ref "HEAD_RAIL") (pin "2") (pinfunction "S_2") (pintype "passive"))
      (node (ref "HEAD_RELE") (pin "2") (pinfunction "S_2") (pintype "passive"))
      (node (ref "HEAD_RUDDER") (pin "2") (pinfunction "S_2") (pintype "passive"))
      (node (ref "IC1") (pin "1") (pinfunction "VDD_1") (pintype "power_in"))
      (node (ref "IC1") (pin "2") (pinfunction "PS_2") (pintype "input"))
      (node (ref "IC1") (pin "4") (pinfunction "CSB_4") (pintype "input"))
      (node (ref "IC1") (pin "5") (pinfunction "CSB_5") (pintype "input"))
      (node (ref "JP2") (pin "4") (pinfunction "VCC_4") (pintype "passive"))
      (node (ref "JP4") (pin "8") (pinfunction "8_8") (pintype "passive"))
      (node (ref "R1") (pin "1") (pinfunction "1_1") (pintype "passive"))
      (node (ref "R13") (pin "2") (pinfunction "2_2") (pintype "passive"))
      (node (ref "R15") (pin "2") (pinfunction "2_2") (pintype "passive"))
      (node (ref "R16") (pin "1") (pinfunction "1_1") (pintype "passive"))
      (node (ref "R17") (pin "1") (pinfunction "1_1") (pintype "passive"))
      (node (ref "R18") (pin "1") (pinfunction "1_1") (pintype "passive"))
      (node (ref "R2") (pin "2") (pinfunction "2_2") (pintype "passive"))
      (node (ref "R20") (pin "2") (pinfunction "2_2") (pintype "passive"))
      (node (ref "R21") (pin "2") (pinfunction "2_2") (pintype "passive"))
      (node (ref "R22") (pin "2") (pinfunction "2_2") (pintype "passive"))
      (node (ref "R3") (pin "1") (pinfunction "1_1") (pintype "passive"))
      (node (ref "R5") (pin "1") (pinfunction "1_1") (pintype "passive"))
      (node (ref "R6") (pin "1") (pinfunction "1_1") (pintype "passive"))
      (node (ref "SJ1") (pin "1") (pinfunction "1_1") (pintype "passive"))
      (node (ref "STM32F401RBT6") (pin "13") (pinfunction "VDDA_13") (pintype "power_in"))
      (node (ref "STM32F401RBT6") (pin "19") (pinfunction "VDD_4_19") (pintype "power_in"))
      (node (ref "STM32F401RBT6") (pin "32") (pinfunction "VDD_1_32") (pintype "power_in"))
      (node (ref "STM32F401RBT6") (pin "48") (pinfunction "VDD_2_48") (pintype "power_in"))
      (node (ref "STM32F401RBT6") (pin "64") (pinfunction "VDD_3_64") (pintype "power_in"))
      (node (ref "U$2") (pin "1") (pinfunction "VCC_1") (pintype "bidirectional"))
      (node (ref "U$3") (pin "8") (pinfunction "VCC_8") (pintype "bidirectional"))
      (node (ref "U$5") (pin "23_VCC") (pinfunction "23_VCC_23_VCC") (pintype "bidirectional"))
      (node (ref "U$8") (pin "8") (pinfunction "3.3V_8") (pintype "power_in"))
      (node (ref "U1") (pin "3") (pinfunction "VOUT_3") (pintype "output"))
      (node (ref "U2") (pin "4") (pinfunction "VCC_4") (pintype "bidirectional"))
      (node (ref "U3") (pin "13") (pinfunction "VDD_13") (pintype "bidirectional"))
      (node (ref "U3") (pin "3") (pinfunction "VDD_3") (pintype "bidirectional"))
      (node (ref "U3") (pin "8") (pinfunction "VLOGIC_8") (pintype "bidirectional"))
    )
    (net (code "69") (name "unconnected-(IC1-SDO-Pad6)") (class "Default")
      (node (ref "IC1") (pin "6") (pinfunction "SDO_6") (pintype "output"))
    )
    (net (code "70") (name "unconnected-(J$1-GND-PadGND@1)") (class "Default")
      (node (ref "J$1") (pin "GND@1") (pinfunction "GND_GND@1") (pintype "bidirectional"))
    )
    (net (code "71") (name "unconnected-(J$1-GND-PadGND@2)") (class "Default")
      (node (ref "J$1") (pin "GND@2") (pinfunction "GND_GND@2") (pintype "bidirectional"))
    )
    (net (code "72") (name "unconnected-(J$1-GND-PadGND@3)") (class "Default")
      (node (ref "J$1") (pin "GND@3") (pinfunction "GND_GND@3") (pintype "bidirectional"))
    )
    (net (code "73") (name "unconnected-(J1-PAD1-PadNC1)") (class "Default")
      (node (ref "J1") (pin "NC1") (pinfunction "PAD1_NC1") (pintype "bidirectional"))
    )
    (net (code "74") (name "unconnected-(J1-PAD2-PadNC2)") (class "Default")
      (node (ref "J1") (pin "NC2") (pinfunction "PAD2_NC2") (pintype "bidirectional"))
    )
    (net (code "75") (name "unconnected-(JP2-CTS-Pad5)") (class "Default")
      (node (ref "JP2") (pin "5") (pinfunction "CTS_5") (pintype "passive"))
    )
    (net (code "76") (name "unconnected-(JP2-DTR-Pad1)") (class "Default")
      (node (ref "JP2") (pin "1") (pinfunction "DTR_1") (pintype "passive"))
    )
    (net (code "77") (name "unconnected-(S1-O-Pad1)") (class "Default")
      (node (ref "S1") (pin "1") (pinfunction "O_1") (pintype "passive"))
    )
    (net (code "78") (name "unconnected-(STM32F401RBT6C-PA0-Pad14)") (class "Default")
      (node (ref "STM32F401RBT6") (pin "14") (pinfunction "PA0_14") (pintype "bidirectional"))
    )
    (net (code "79") (name "unconnected-(STM32F401RBT6C-PA1-Pad15)") (class "Default")
      (node (ref "STM32F401RBT6") (pin "15") (pinfunction "PA1_15") (pintype "bidirectional"))
    )
    (net (code "80") (name "unconnected-(STM32F401RBT6C-PA4-Pad20)") (class "Default")
      (node (ref "STM32F401RBT6") (pin "20") (pinfunction "PA4_20") (pintype "bidirectional"))
    )
    (net (code "81") (name "unconnected-(STM32F401RBT6C-PA5-Pad21)") (class "Default")
      (node (ref "STM32F401RBT6") (pin "21") (pinfunction "PA5_21") (pintype "bidirectional"))
    )
    (net (code "82") (name "unconnected-(STM32F401RBT6C-PA6-Pad22)") (class "Default")
      (node (ref "STM32F401RBT6") (pin "22") (pinfunction "PA6_22") (pintype "bidirectional"))
    )
    (net (code "83") (name "unconnected-(STM32F401RBT6C-PA7-Pad23)") (class "Default")
      (node (ref "STM32F401RBT6") (pin "23") (pinfunction "PA7_23") (pintype "bidirectional"))
    )
    (net (code "84") (name "unconnected-(STM32F401RBT6D-PB11-Pad30)") (class "Default")
      (node (ref "STM32F401RBT6") (pin "30") (pinfunction "PB11_30") (pintype "bidirectional"))
    )
    (net (code "85") (name "unconnected-(STM32F401RBT6E-PB2-Pad28)") (class "Default")
      (node (ref "STM32F401RBT6") (pin "28") (pinfunction "PB2_28") (pintype "bidirectional"))
    )
    (net (code "86") (name "unconnected-(STM32F401RBT6E-PB5-Pad57)") (class "Default")
      (node (ref "STM32F401RBT6") (pin "57") (pinfunction "PB5_57") (pintype "bidirectional"))
    )
    (net (code "87") (name "unconnected-(STM32F401RBT6H-PD0{slash}OSC<=-Pad5)") (class "Default")
      (node (ref "STM32F401RBT6") (pin "5") (pinfunction "PD0/OSC<=_5") (pintype "bidirectional"))
    )
    (net (code "88") (name "unconnected-(STM32F401RBT6H-PD1{slash}OSC=>-Pad6)") (class "Default")
      (node (ref "STM32F401RBT6") (pin "6") (pinfunction "PD1/OSC=>_6") (pintype "bidirectional"))
    )
    (net (code "89") (name "unconnected-(U$1-IO3-Pad4)") (class "Default")
      (node (ref "U$1") (pin "4") (pinfunction "IO3_4") (pintype "bidirectional"))
    )
    (net (code "90") (name "unconnected-(U$1-IO4-Pad6)") (class "Default")
      (node (ref "U$1") (pin "6") (pinfunction "IO4_6") (pintype "bidirectional"))
    )
    (net (code "91") (name "unconnected-(U$2-RTCK-Pad7)") (class "Default")
      (node (ref "U$2") (pin "7") (pinfunction "RTCK_7") (pintype "bidirectional"))
    )
    (net (code "92") (name "unconnected-(U$5-Pad1_RESERVED)") (class "Default")
      (node (ref "U$5") (pin "1_RESERVED") (pinfunction "1_RESERVED_1_RESERVED") (pintype "bidirectional"))
    )
    (net (code "93") (name "unconnected-(U$5-Pad2_SS_N)") (class "Default")
      (node (ref "U$5") (pin "2_SS_N") (pinfunction "2_SS_N_2_SS_N") (pintype "bidirectional"))
    )
    (net (code "94") (name "unconnected-(U$5-Pad14_MOSI{slash}CFG_COM0)") (class "Default")
      (node (ref "U$5") (pin "14_MOSI/CFG_COM0") (pinfunction "14_MOSI/CFG_COM0_14_MOSI/CFG_COM0") (pintype "bidirectional"))
    )
    (net (code "95") (name "unconnected-(U$5-Pad15_MISO{slash}CFG_COM1)") (class "Default")
      (node (ref "U$5") (pin "15_MISO/CFG_COM1") (pinfunction "15_MISO/CFG_COM1_15_MISO/CFG_COM1") (pintype "bidirectional"))
    )
    (net (code "96") (name "unconnected-(U$5-Pad16_CFG_CPS0{slash}SCK)") (class "Default")
      (node (ref "U$5") (pin "16_CFG_CPS0/SCK") (pinfunction "16_CFG_CPS0/SCK_16_CFG_CPS0/SCK") (pintype "bidirectional"))
    )
    (net (code "97") (name "unconnected-(U$5-Pad17_RESERVED)") (class "Default")
      (node (ref "U$5") (pin "17_RESERVED") (pinfunction "17_RESERVED_17_RESERVED") (pintype "bidirectional"))
    )
    (net (code "98") (name "unconnected-(U$5-Pad22_V_BCKP)") (class "Default")
      (node (ref "U$5") (pin "22_V_BCKP") (pinfunction "22_V_BCKP_22_V_BCKP") (pintype "bidirectional"))
    )
    (net (code "99") (name "unconnected-(U$6-IO3-Pad4)") (class "Default")
      (node (ref "U$6") (pin "4") (pinfunction "IO3_4") (pintype "bidirectional"))
    )
    (net (code "100") (name "unconnected-(U$6-IO4-Pad6)") (class "Default")
      (node (ref "U$6") (pin "6") (pinfunction "IO4_6") (pintype "bidirectional"))
    )
    (net (code "101") (name "unconnected-(U$8-DIO1-Pad3)") (class "Default")
      (node (ref "U$8") (pin "3") (pinfunction "DIO1_3") (pintype "bidirectional"))
    )
    (net (code "102") (name "unconnected-(U$8-DIO2-Pad4)") (class "Default")
      (node (ref "U$8") (pin "4") (pinfunction "DIO2_4") (pintype "bidirectional"))
    )
    (net (code "103") (name "unconnected-(U$8-DIO3-Pad5)") (class "Default")
      (node (ref "U$8") (pin "5") (pinfunction "DIO3_5") (pintype "bidirectional"))
    )
    (net (code "104") (name "unconnected-(U$8-DIO4-Pad6)") (class "Default")
      (node (ref "U$8") (pin "6") (pinfunction "DIO4_6") (pintype "bidirectional"))
    )
    (net (code "105") (name "unconnected-(U$8-DIO5-Pad7)") (class "Default")
      (node (ref "U$8") (pin "7") (pinfunction "DIO5_7") (pintype "bidirectional"))
    )
    (net (code "106") (name "unconnected-(U3-CLKOUT-Pad22)") (class "Default")
      (node (ref "U3") (pin "22") (pinfunction "CLKOUT_22") (pintype "bidirectional"))
    )
    (net (code "107") (name "unconnected-(U3-E_SCL-Pad7)") (class "Default")
      (node (ref "U3") (pin "7") (pinfunction "E_SCL_7") (pintype "bidirectional"))
    )
    (net (code "108") (name "unconnected-(U3-E_SDA-Pad6)") (class "Default")
      (node (ref "U3") (pin "6") (pinfunction "E_SDA_6") (pintype "bidirectional"))
    )
  )
)
